# MCU.net
KiCad netlist of a schematic drawn in Altium Designer
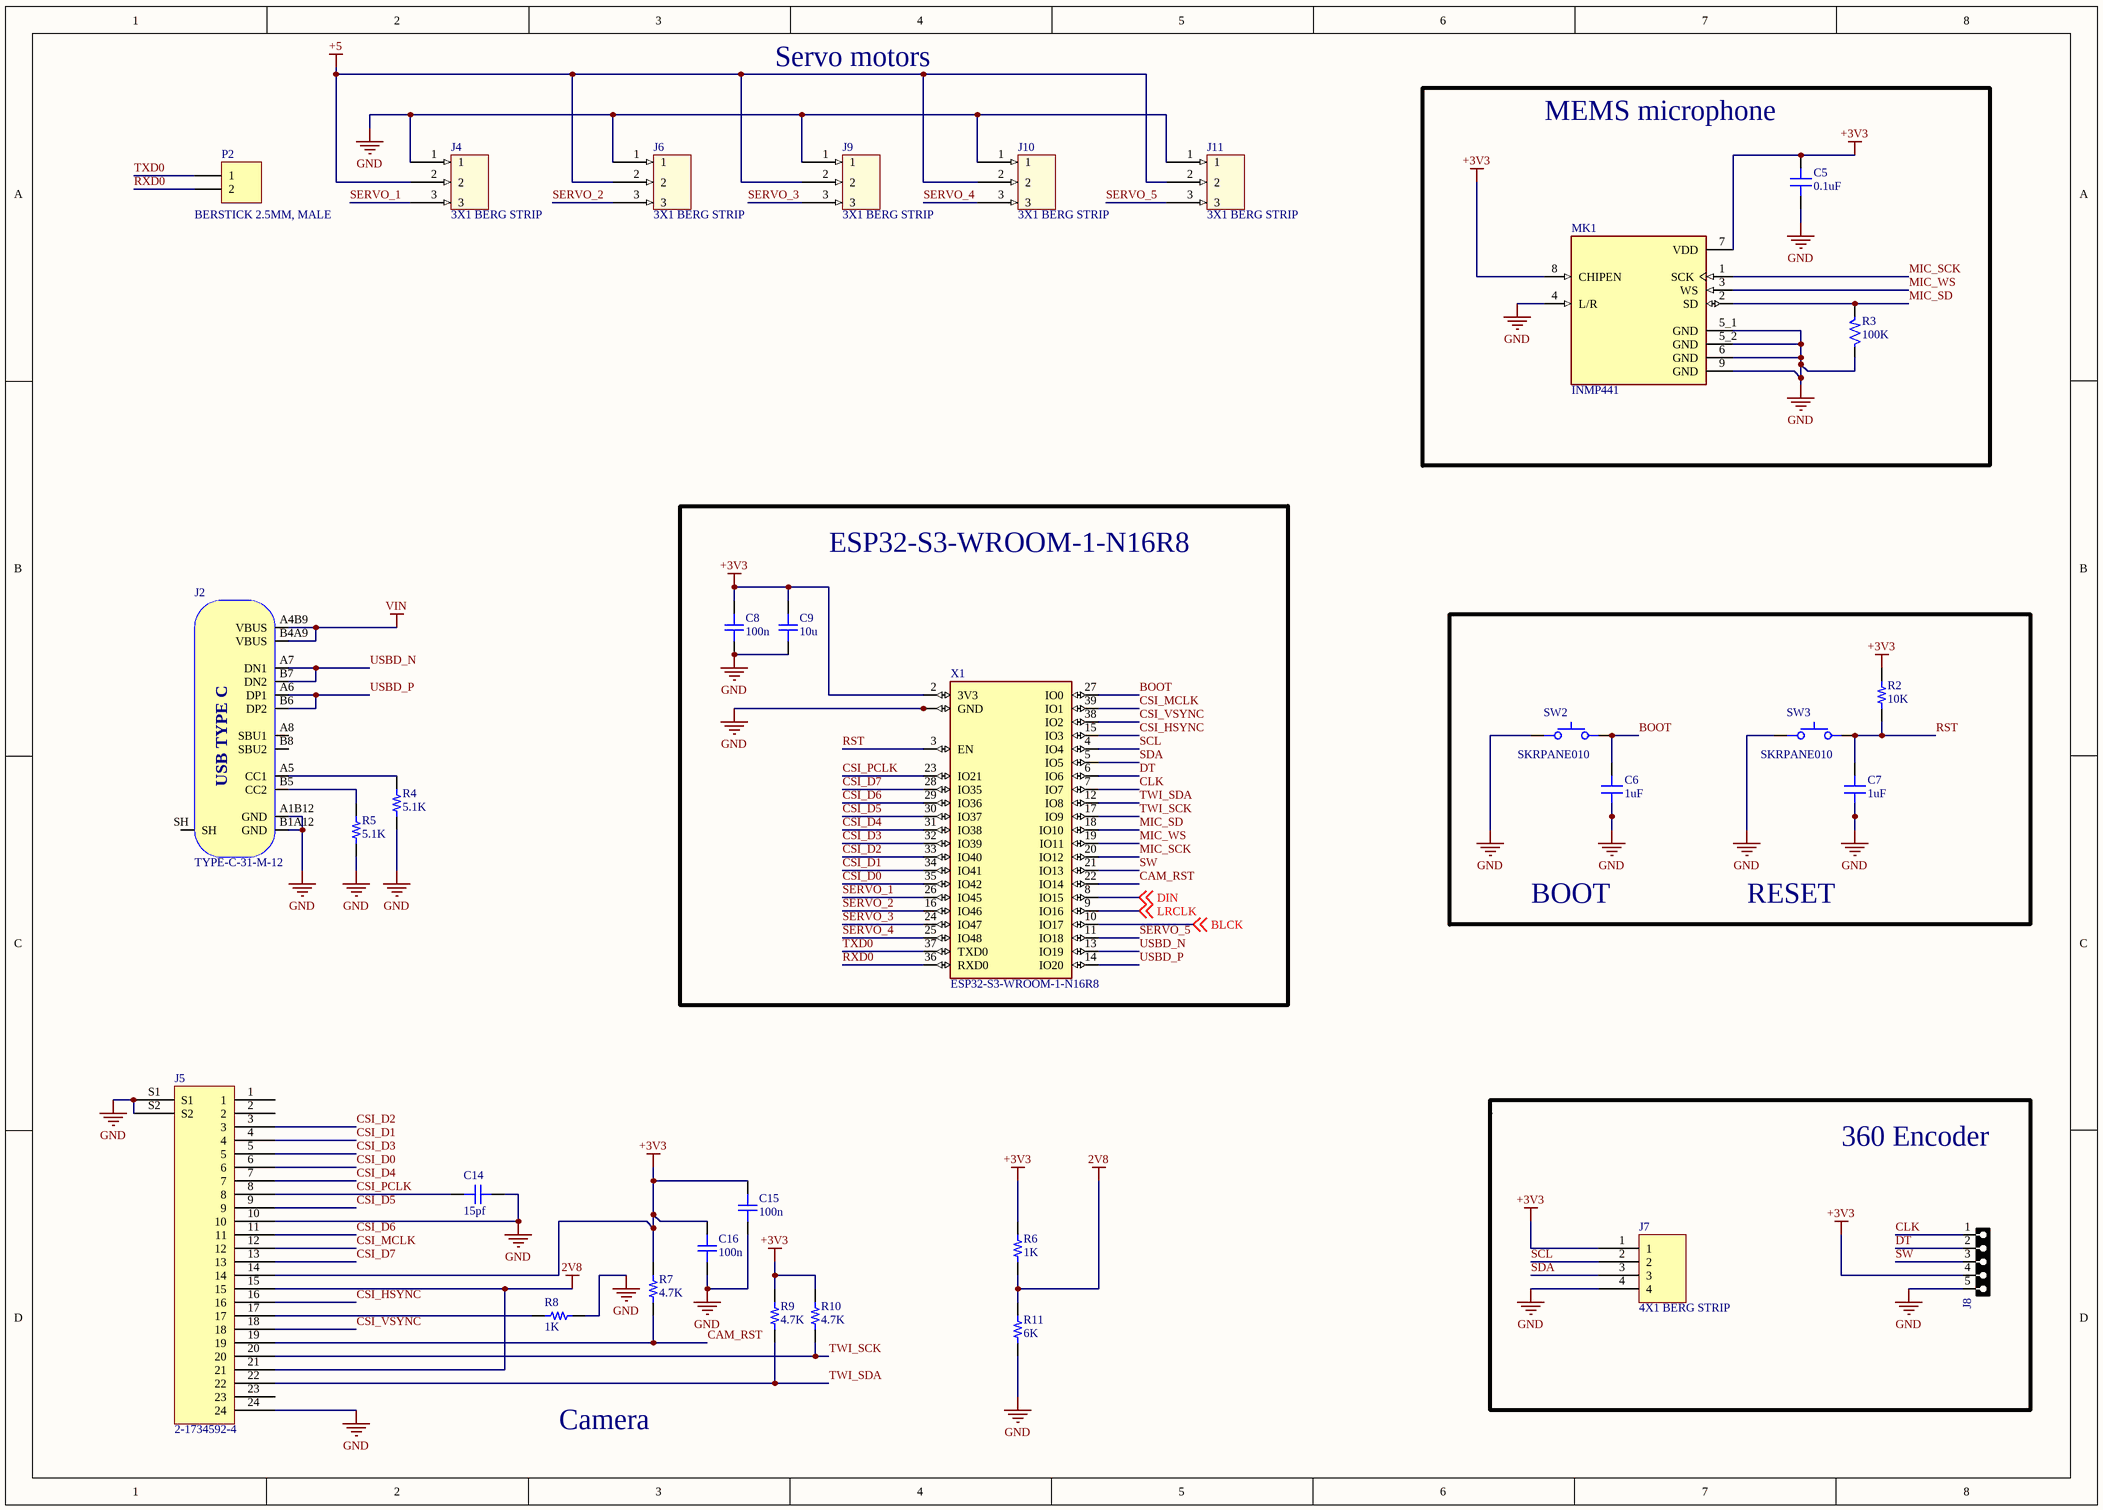
[diagram p0: MCU.SchDoc]

(export (version "E")
  (design (tool "Eeschema 10.0.6"))
  (components
    (comp (ref "C5")
      (value "0.1uF")
      (footprint "CAP 0402_1005")
      (description "SMT Capacitor")
      (libsource (lib "Capacitor") (part "Cap 0402"))
    )
    (comp (ref "C6")
      (value "1uF")
      (footprint "CAP 0402_1005")
      (description "SMT Capacitor")
      (libsource (lib "Capacitor") (part "Cap 0402"))
    )
    (comp (ref "C7")
      (value "1uF")
      (footprint "CAP 0402_1005")
      (description "SMT Capacitor")
      (libsource (lib "Capacitor") (part "Cap 0402"))
    )
    (comp (ref "C8")
      (value "100n")
      (footprint "CAP_0402")
      (description "Capacitor SMD 0402 50V")
      (fields
        (field (name "MANUFACTURER") "Samsung")
        (field (name "MANUFACTURER PART NUMBER") "CL05B104KO5NNNC")
      )
      (libsource (lib "ESP32_USB_Dongle") (part "CAP_0402_50V_1"))
    )
    (comp (ref "C9")
      (value "10u")
      (footprint "CAP_0603")
      (description "Capacitor SMD 0603 10V")
      (fields
        (field (name "MANUFACTURER") "Samsung")
        (field (name "MANUFACTURER PART NUMBER") "CL10A106KP8NNNC")
      )
      (libsource (lib "ESP32_USB_Dongle") (part "CAP_0603_10V"))
    )
    (comp (ref "C14")
      (value "15pf")
      (footprint "CAP_0402")
      (description "Capacitor SMD 0402 50V")
      (fields
        (field (name "MANUFACTURER") "Samsung")
        (field (name "MANUFACTURER PART NUMBER") "CL05C100JB5NNNC")
      )
      (libsource (lib "ESP32_USB_Dongle") (part "CAP_0402_50V_2"))
    )
    (comp (ref "C15")
      (value "100n")
      (footprint "CAP_0402")
      (description "Capacitor SMD 0402 50V")
      (fields
        (field (name "MANUFACTURER") "Samsung")
        (field (name "MANUFACTURER PART NUMBER") "CL05B104KO5NNNC")
      )
      (libsource (lib "ESP32_USB_Dongle") (part "CAP_0402_50V_1"))
    )
    (comp (ref "C16")
      (value "100n")
      (footprint "CAP_0402")
      (description "Capacitor SMD 0402 50V")
      (fields
        (field (name "MANUFACTURER") "Samsung")
        (field (name "MANUFACTURER PART NUMBER") "CL05B104KO5NNNC")
      )
      (libsource (lib "ESP32_USB_Dongle") (part "CAP_0402_50V_1"))
    )
    (comp (ref "J2")
      (value "TYPE-C-31-M-12")
      (footprint "TYPE-C-31-M-12")
      (description "USB Type C Connector Horizontal SMT")
      (fields (field (name "MANUFACTURER") "Koren Hroparts"))
      (libsource (lib "ESP32_USB_Dongle") (part "TYPE-C-31-M-12"))
    )
    (comp (ref "J4")
      (value "3X1 BERG STRIP")
      (footprint "CON3_100_40D72_TH_ST-MALE")
      (description "3 Pins, 1 Row 2.54mm Pitch, Straight bergstrip, Male")
      (fields (field (name "MANUFACTURER PART NUMBER") "RKI-1140") (field (name "MANUFACTURER") "NA"))
      (libsource (lib "ESTEEMPCBLIB") (part "CON-BS-PLG_3X1-100-ST-TH"))
    )
    (comp (ref "J5")
      (value "2-1734592-4")
      (footprint "CON24_19_2-1734592-4_SMD_RA")
      (description "FFC & FPC Connectors FPC CONN 0.5MM PITCH B/C 24P")
      (fields
        (field (name "MANUFACTURER") "TE Connectivity")
        (field (name "MATING PART NUMBER") "0151660259")
      )
      (libsource (lib "ESTEEMPCBLIB") (part "CON-PLG-FPC_24X1-19-RA-BC-SMD"))
    )
    (comp (ref "J6")
      (value "3X1 BERG STRIP")
      (footprint "CON3_100_40D72_TH_ST-MALE")
      (description "3 Pins, 1 Row 2.54mm Pitch, Straight bergstrip, Male")
      (fields (field (name "MANUFACTURER PART NUMBER") "RKI-1140") (field (name "MANUFACTURER") "NA"))
      (libsource (lib "ESTEEMPCBLIB") (part "CON-BS-PLG_3X1-100-ST-TH"))
    )
    (comp (ref "J7")
      (value "4X1 BERG STRIP")
      (footprint "CON4_100_40D72_TH_ST_MALE")
      (description "4 Pins, 1 Row 2.54mm Pitch, Straight bergstrip, Male")
      (fields (field (name "MANUFACTURER") "NA"))
      (libsource (lib "ESTEEMPCBLIB") (part "CON-BS-PLG_4X1-100-ST-TH"))
    )
    (comp (ref "J8")
      (value "HDRF5")
      (footprint "HDRLP_F_1X5")
      (description "CONN, HEADER, Male, pitch: 2.54mm, 5POS")
      (libsource (lib "Conn Header") (part "HDRLP_F_1X5"))
    )
    (comp (ref "J9")
      (value "3X1 BERG STRIP")
      (footprint "CON3_100_40D72_TH_ST-MALE")
      (description "3 Pins, 1 Row 2.54mm Pitch, Straight bergstrip, Male")
      (fields (field (name "MANUFACTURER PART NUMBER") "RKI-1140") (field (name "MANUFACTURER") "NA"))
      (libsource (lib "ESTEEMPCBLIB") (part "CON-BS-PLG_3X1-100-ST-TH"))
    )
    (comp (ref "J10")
      (value "3X1 BERG STRIP")
      (footprint "CON3_100_40D72_TH_ST-MALE")
      (description "3 Pins, 1 Row 2.54mm Pitch, Straight bergstrip, Male")
      (fields (field (name "MANUFACTURER PART NUMBER") "RKI-1140") (field (name "MANUFACTURER") "NA"))
      (libsource (lib "ESTEEMPCBLIB") (part "CON-BS-PLG_3X1-100-ST-TH"))
    )
    (comp (ref "J11")
      (value "3X1 BERG STRIP")
      (footprint "CON3_100_40D72_TH_ST-MALE")
      (description "3 Pins, 1 Row 2.54mm Pitch, Straight bergstrip, Male")
      (fields (field (name "MANUFACTURER PART NUMBER") "RKI-1140") (field (name "MANUFACTURER") "NA"))
      (libsource (lib "ESTEEMPCBLIB") (part "CON-BS-PLG_3X1-100-ST-TH"))
    )
    (comp (ref "MK1")
      (value "INMP441")
      (footprint "MIC_INMP441")
      (description "EVAL BOARD MEMS MIC INMP441")
      (fields (field (name "MF") "TDK InvenSense"))
      (libsource (lib "INMP441") (part "INMP441"))
    )
    (comp (ref "P2")
      (value "BERSTICK 2.5MM, MALE")
      (footprint "CON2_100_43D62_TH_ST")
      (description "2 Pins, 1 Row 2.54mm Pitch, Straight bergstrip, Male")
      (fields (field (name "MANUFACTURER PART NUMBER") "NA") (field (name "MANUFACTURER") "Samtec"))
      (libsource (lib "ESTEEMPCBLIB") (part "CON-BS-PLG_2X1-100-ST-TH"))
    )
    (comp (ref "R2")
      (value "10K")
      (footprint "RES 0402_1005")
      (description "SMT Resistor")
      (libsource (lib "Resistor") (part "Res 0402"))
    )
    (comp (ref "R3")
      (value "100K")
      (footprint "RES_0603")
      (description "100 kOhms ±1% 0.1W, 1/10W Chip Resistor 0603 (1608 Metric) Automotive AEC-Q200 Thick Film")
      (fields
        (field (name "MANUFACTURER") "Stackpole Electronics")
        (field (name "MANUFACTURER PART NUMBER") "RMCF0603FT100K")
      )
      (libsource (lib "ESTEEMPCBLIB") (part "RES_100K-0.1W-1%-0603"))
    )
    (comp (ref "R4")
      (value "5.1K")
      (footprint "RES 0402_1005")
      (description "SMT Resistor")
      (libsource (lib "Resistor") (part "Res 0402"))
    )
    (comp (ref "R5")
      (value "5.1K")
      (footprint "RES 0402_1005")
      (description "SMT Resistor")
      (libsource (lib "Resistor") (part "Res 0402"))
    )
    (comp (ref "R6")
      (value "1K")
      (footprint "RES 0402_1005")
      (description "SMT Resistor")
      (libsource (lib "Resistor") (part "Res 0402"))
    )
    (comp (ref "R7")
      (value "4.7K")
      (footprint "RES 0402_1005")
      (description "SMT Resistor")
      (libsource (lib "Resistor") (part "Res 0402"))
    )
    (comp (ref "R8")
      (value "1K")
      (footprint "RES 0402_1005")
      (description "SMT Resistor")
      (libsource (lib "Resistor") (part "Res 0402"))
    )
    (comp (ref "R9")
      (value "4.7K")
      (footprint "RES 0402_1005")
      (description "SMT Resistor")
      (libsource (lib "Resistor") (part "Res 0402"))
    )
    (comp (ref "R10")
      (value "4.7K")
      (footprint "RES 0402_1005")
      (description "SMT Resistor")
      (libsource (lib "Resistor") (part "Res 0402"))
    )
    (comp (ref "R11")
      (value "6K")
      (footprint "RES 0402_1005")
      (description "SMT Resistor")
      (libsource (lib "Resistor") (part "Res 0402"))
    )
    (comp (ref "SW2")
      (value "SKRPANE010")
      (footprint "SKRPANE010")
      (description "Tactile Switch SMD SPST")
      (fields (field (name "MANUFACTURER") "Alps Alpine"))
      (libsource (lib "ESP32_USB_Dongle") (part "SKRPANE010"))
    )
    (comp (ref "SW3")
      (value "SKRPANE010")
      (footprint "SKRPANE010")
      (description "Tactile Switch SMD SPST")
      (fields (field (name "MANUFACTURER") "Alps Alpine"))
      (libsource (lib "ESP32_USB_Dongle") (part "SKRPANE010"))
    )
    (comp (ref "X1")
      (value "ESP32-S3-WROOM-1-N16R8")
      (footprint "ESP32S3WROOM1N8R2")
      (description "Bluetooth, WiFi 802.11b/g/n, Bluetooth v5.0 Transceiver Module 2.4GHz PCB Trace Surface Mount")
      (fields (field (name "MF") "Espressif Systems"))
      (libsource (lib "ESP32-S3-WROOM-1-N16R8") (part "ESP32-S3-WROOM-1-N16R8"))
    )
  )
  (nets
    (net (code "1") (name "+3V3") (class "Default")
      (node (ref "C15") (pin "2") (pinfunction "2_2") (pintype "passive"))
      (node (ref "C16") (pin "2") (pinfunction "2_2") (pintype "passive"))
      (node (ref "C5") (pin "2") (pinfunction "2_2") (pintype "passive"))
      (node (ref "C8") (pin "2") (pinfunction "2_2") (pintype "passive"))
      (node (ref "C9") (pin "2") (pinfunction "2_2") (pintype "passive"))
      (node (ref "J5") (pin "14") (pinfunction "14_14") (pintype "passive"))
      (node (ref "J7") (pin "1") (pinfunction "1_1") (pintype "passive"))
      (node (ref "J8") (pin "4") (pinfunction "4_4") (pintype "passive"))
      (node (ref "MK1") (pin "7") (pinfunction "VDD_7") (pintype "power_in"))
      (node (ref "MK1") (pin "8") (pinfunction "CHIPEN_8") (pintype "input"))
      (node (ref "R10") (pin "2") (pinfunction "2_2") (pintype "passive"))
      (node (ref "R2") (pin "2") (pinfunction "2_2") (pintype "passive"))
      (node (ref "R6") (pin "2") (pinfunction "2_2") (pintype "passive"))
      (node (ref "R7") (pin "2") (pinfunction "2_2") (pintype "passive"))
      (node (ref "R9") (pin "2") (pinfunction "2_2") (pintype "passive"))
      (node (ref "X1") (pin "2") (pinfunction "3V3_2") (pintype "bidirectional"))
    )
    (net (code "2") (name "+5") (class "Default")
      (node (ref "J10") (pin "2") (pinfunction "2_2") (pintype "input"))
      (node (ref "J11") (pin "2") (pinfunction "2_2") (pintype "input"))
      (node (ref "J4") (pin "2") (pinfunction "2_2") (pintype "input"))
      (node (ref "J6") (pin "2") (pinfunction "2_2") (pintype "input"))
      (node (ref "J9") (pin "2") (pinfunction "2_2") (pintype "input"))
    )
    (net (code "3") (name "/BOOT") (class "Default")
      (node (ref "C6") (pin "2") (pinfunction "2_2") (pintype "passive"))
      (node (ref "SW2") (pin "34") (pintype "passive"))
      (node (ref "X1") (pin "27") (pinfunction "IO0_27") (pintype "bidirectional"))
    )
    (net (code "4") (name "/CAM_RST") (class "Default")
      (node (ref "J5") (pin "19") (pinfunction "19_19") (pintype "passive"))
      (node (ref "R7") (pin "1") (pinfunction "1_1") (pintype "passive"))
      (node (ref "X1") (pin "22") (pinfunction "IO14_22") (pintype "bidirectional"))
    )
    (net (code "5") (name "/CLK") (class "Default")
      (node (ref "J8") (pin "1") (pinfunction "1_1") (pintype "passive"))
      (node (ref "X1") (pin "7") (pinfunction "IO7_7") (pintype "bidirectional"))
    )
    (net (code "6") (name "/CSI_D0") (class "Default")
      (node (ref "J5") (pin "6") (pinfunction "6_6") (pintype "passive"))
      (node (ref "X1") (pin "35") (pinfunction "IO42_35") (pintype "bidirectional"))
    )
    (net (code "7") (name "/CSI_D1") (class "Default")
      (node (ref "J5") (pin "4") (pinfunction "4_4") (pintype "passive"))
      (node (ref "X1") (pin "34") (pinfunction "IO41_34") (pintype "bidirectional"))
    )
    (net (code "8") (name "/CSI_D2") (class "Default")
      (node (ref "J5") (pin "3") (pinfunction "3_3") (pintype "passive"))
      (node (ref "X1") (pin "33") (pinfunction "IO40_33") (pintype "bidirectional"))
    )
    (net (code "9") (name "/CSI_D3") (class "Default")
      (node (ref "J5") (pin "5") (pinfunction "5_5") (pintype "passive"))
      (node (ref "X1") (pin "32") (pinfunction "IO39_32") (pintype "bidirectional"))
    )
    (net (code "10") (name "/CSI_D4") (class "Default")
      (node (ref "J5") (pin "7") (pinfunction "7_7") (pintype "passive"))
      (node (ref "X1") (pin "31") (pinfunction "IO38_31") (pintype "bidirectional"))
    )
    (net (code "11") (name "/CSI_D5") (class "Default")
      (node (ref "J5") (pin "9") (pinfunction "9_9") (pintype "passive"))
      (node (ref "X1") (pin "30") (pinfunction "IO37_30") (pintype "bidirectional"))
    )
    (net (code "12") (name "/CSI_D6") (class "Default")
      (node (ref "J5") (pin "11") (pinfunction "11_11") (pintype "passive"))
      (node (ref "X1") (pin "29") (pinfunction "IO36_29") (pintype "bidirectional"))
    )
    (net (code "13") (name "/CSI_D7") (class "Default")
      (node (ref "J5") (pin "13") (pinfunction "13_13") (pintype "passive"))
      (node (ref "X1") (pin "28") (pinfunction "IO35_28") (pintype "bidirectional"))
    )
    (net (code "14") (name "/CSI_HSYNC") (class "Default")
      (node (ref "J5") (pin "16") (pinfunction "16_16") (pintype "passive"))
      (node (ref "X1") (pin "15") (pinfunction "IO3_15") (pintype "bidirectional"))
    )
    (net (code "15") (name "/CSI_MCLK") (class "Default")
      (node (ref "J5") (pin "12") (pinfunction "12_12") (pintype "passive"))
      (node (ref "X1") (pin "39") (pinfunction "IO1_39") (pintype "bidirectional"))
    )
    (net (code "16") (name "/CSI_PCLK") (class "Default")
      (node (ref "C14") (pin "2") (pinfunction "2_2") (pintype "passive"))
      (node (ref "J5") (pin "8") (pinfunction "8_8") (pintype "passive"))
      (node (ref "X1") (pin "23") (pinfunction "IO21_23") (pintype "bidirectional"))
    )
    (net (code "17") (name "/CSI_VSYNC") (class "Default")
      (node (ref "J5") (pin "18") (pinfunction "18_18") (pintype "passive"))
      (node (ref "X1") (pin "38") (pinfunction "IO2_38") (pintype "bidirectional"))
    )
    (net (code "18") (name "/DT") (class "Default")
      (node (ref "J8") (pin "2") (pinfunction "2_2") (pintype "passive"))
      (node (ref "X1") (pin "6") (pinfunction "IO6_6") (pintype "bidirectional"))
    )
    (net (code "19") (name "/MIC_SCK") (class "Default")
      (node (ref "MK1") (pin "1") (pinfunction "SCK_1") (pintype "input"))
      (node (ref "X1") (pin "20") (pinfunction "IO12_20") (pintype "bidirectional"))
    )
    (net (code "20") (name "/MIC_SD") (class "Default")
      (node (ref "MK1") (pin "2") (pinfunction "SD_2") (pintype "bidirectional"))
      (node (ref "R3") (pin "2") (pinfunction "2_2") (pintype "passive"))
      (node (ref "X1") (pin "18") (pinfunction "IO10_18") (pintype "bidirectional"))
    )
    (net (code "21") (name "/MIC_WS") (class "Default")
      (node (ref "MK1") (pin "3") (pinfunction "WS_3") (pintype "input"))
      (node (ref "X1") (pin "19") (pinfunction "IO11_19") (pintype "bidirectional"))
    )
    (net (code "22") (name "/RST") (class "Default")
      (node (ref "C7") (pin "2") (pinfunction "2_2") (pintype "passive"))
      (node (ref "R2") (pin "1") (pinfunction "1_1") (pintype "passive"))
      (node (ref "SW3") (pin "34") (pintype "passive"))
      (node (ref "X1") (pin "3") (pinfunction "EN_3") (pintype "bidirectional"))
    )
    (net (code "23") (name "/RXD0") (class "Default")
      (node (ref "P2") (pin "2") (pinfunction "2_2") (pintype "passive"))
      (node (ref "X1") (pin "36") (pinfunction "RXD0_36") (pintype "bidirectional"))
    )
    (net (code "24") (name "/SCL") (class "Default")
      (node (ref "J7") (pin "2") (pinfunction "2_2") (pintype "passive"))
      (node (ref "X1") (pin "4") (pinfunction "IO4_4") (pintype "bidirectional"))
    )
    (net (code "25") (name "/SDA") (class "Default")
      (node (ref "J7") (pin "3") (pinfunction "3_3") (pintype "passive"))
      (node (ref "X1") (pin "5") (pinfunction "IO5_5") (pintype "bidirectional"))
    )
    (net (code "26") (name "/SERVO_1") (class "Default")
      (node (ref "J4") (pin "3") (pinfunction "3_3") (pintype "input"))
      (node (ref "X1") (pin "26") (pinfunction "IO45_26") (pintype "bidirectional"))
    )
    (net (code "27") (name "/SERVO_2") (class "Default")
      (node (ref "J6") (pin "3") (pinfunction "3_3") (pintype "input"))
      (node (ref "X1") (pin "16") (pinfunction "IO46_16") (pintype "bidirectional"))
    )
    (net (code "28") (name "/SERVO_3") (class "Default")
      (node (ref "J9") (pin "3") (pinfunction "3_3") (pintype "input"))
      (node (ref "X1") (pin "24") (pinfunction "IO47_24") (pintype "bidirectional"))
    )
    (net (code "29") (name "/SERVO_4") (class "Default")
      (node (ref "J10") (pin "3") (pinfunction "3_3") (pintype "input"))
      (node (ref "X1") (pin "25") (pinfunction "IO48_25") (pintype "bidirectional"))
    )
    (net (code "30") (name "/SERVO_5") (class "Default")
      (node (ref "J11") (pin "3") (pinfunction "3_3") (pintype "input"))
      (node (ref "X1") (pin "11") (pinfunction "IO18_11") (pintype "bidirectional"))
    )
    (net (code "31") (name "/SW") (class "Default")
      (node (ref "J8") (pin "3") (pinfunction "3_3") (pintype "passive"))
      (node (ref "X1") (pin "21") (pinfunction "IO13_21") (pintype "bidirectional"))
    )
    (net (code "32") (name "/TWI_SCK") (class "Default")
      (node (ref "J5") (pin "20") (pinfunction "20_20") (pintype "passive"))
      (node (ref "R10") (pin "1") (pinfunction "1_1") (pintype "passive"))
      (node (ref "X1") (pin "17") (pinfunction "IO9_17") (pintype "bidirectional"))
    )
    (net (code "33") (name "/TWI_SDA") (class "Default")
      (node (ref "J5") (pin "22") (pinfunction "22_22") (pintype "passive"))
      (node (ref "R9") (pin "1") (pinfunction "1_1") (pintype "passive"))
      (node (ref "X1") (pin "12") (pinfunction "IO8_12") (pintype "bidirectional"))
    )
    (net (code "34") (name "/TXD0") (class "Default")
      (node (ref "P2") (pin "1") (pinfunction "1_1") (pintype "passive"))
      (node (ref "X1") (pin "37") (pinfunction "TXD0_37") (pintype "bidirectional"))
    )
    (net (code "35") (name "/USBD_N") (class "Default")
      (node (ref "J2") (pin "A7") (pinfunction "DN1_A7") (pintype "bidirectional"))
      (node (ref "J2") (pin "B7") (pinfunction "DN2_B7") (pintype "bidirectional"))
      (node (ref "X1") (pin "13") (pinfunction "IO19_13") (pintype "bidirectional"))
    )
    (net (code "36") (name "/USBD_P") (class "Default")
      (node (ref "J2") (pin "A6") (pinfunction "DP1_A6") (pintype "bidirectional"))
      (node (ref "J2") (pin "B6") (pinfunction "DP2_B6") (pintype "bidirectional"))
      (node (ref "X1") (pin "14") (pinfunction "IO20_14") (pintype "bidirectional"))
    )
    (net (code "37") (name "2V8") (class "Default")
      (node (ref "J5") (pin "15") (pinfunction "15_15") (pintype "passive"))
      (node (ref "J5") (pin "21") (pinfunction "21_21") (pintype "passive"))
      (node (ref "R11") (pin "2") (pinfunction "2_2") (pintype "passive"))
      (node (ref "R6") (pin "1") (pinfunction "1_1") (pintype "passive"))
    )
    (net (code "38") (name "BLCK") (class "Default")
      (node (ref "X1") (pin "10") (pinfunction "IO17_10") (pintype "bidirectional"))
    )
    (net (code "39") (name "DIN") (class "Default")
      (node (ref "X1") (pin "8") (pinfunction "IO15_8") (pintype "bidirectional"))
    )
    (net (code "40") (name "GND") (class "Default")
      (node (ref "C14") (pin "1") (pinfunction "1_1") (pintype "passive"))
      (node (ref "C15") (pin "1") (pinfunction "1_1") (pintype "passive"))
      (node (ref "C16") (pin "1") (pinfunction "1_1") (pintype "passive"))
      (node (ref "C5") (pin "1") (pinfunction "1_1") (pintype "passive"))
      (node (ref "C6") (pin "1") (pinfunction "1_1") (pintype "passive"))
      (node (ref "C7") (pin "1") (pinfunction "1_1") (pintype "passive"))
      (node (ref "C8") (pin "1") (pinfunction "1_1") (pintype "passive"))
      (node (ref "C9") (pin "1") (pinfunction "1_1") (pintype "passive"))
      (node (ref "J10") (pin "1") (pinfunction "1_1") (pintype "input"))
      (node (ref "J11") (pin "1") (pinfunction "1_1") (pintype "input"))
      (node (ref "J2") (pin "A1B12") (pinfunction "GND_A1B12") (pintype "power_in"))
      (node (ref "J2") (pin "B1A12") (pinfunction "GND_B1A12") (pintype "power_in"))
      (node (ref "J4") (pin "1") (pinfunction "1_1") (pintype "input"))
      (node (ref "J5") (pin "10") (pinfunction "10_10") (pintype "passive"))
      (node (ref "J5") (pin "24") (pinfunction "24_24") (pintype "passive"))
      (node (ref "J5") (pin "S1") (pinfunction "S1_S1") (pintype "passive"))
      (node (ref "J5") (pin "S2") (pinfunction "S2_S2") (pintype "passive"))
      (node (ref "J6") (pin "1") (pinfunction "1_1") (pintype "input"))
      (node (ref "J7") (pin "4") (pinfunction "4_4") (pintype "passive"))
      (node (ref "J8") (pin "5") (pinfunction "5_5") (pintype "passive"))
      (node (ref "J9") (pin "1") (pinfunction "1_1") (pintype "input"))
      (node (ref "MK1") (pin "4") (pinfunction "L/R_4") (pintype "input"))
      (node (ref "MK1") (pin "5_1") (pinfunction "GND_5_1") (pintype "power_in"))
      (node (ref "MK1") (pin "5_2") (pinfunction "GND_5_2") (pintype "power_in"))
      (node (ref "MK1") (pin "6") (pinfunction "GND_6") (pintype "power_in"))
      (node (ref "MK1") (pin "9") (pinfunction "GND_9") (pintype "power_in"))
      (node (ref "R11") (pin "1") (pinfunction "1_1") (pintype "passive"))
      (node (ref "R3") (pin "1") (pinfunction "1_1") (pintype "passive"))
      (node (ref "R4") (pin "1") (pinfunction "1_1") (pintype "passive"))
      (node (ref "R5") (pin "1") (pinfunction "1_1") (pintype "passive"))
      (node (ref "R8") (pin "1") (pinfunction "1_1") (pintype "passive"))
      (node (ref "SW2") (pin "12") (pintype "passive"))
      (node (ref "SW3") (pin "12") (pintype "passive"))
      (node (ref "X1") (pin "1") (pinfunction "GND_1") (pintype "bidirectional"))
      (node (ref "X1") (pin "40") (pinfunction "GND_40") (pintype "bidirectional"))
      (node (ref "X1") (pin "41") (pinfunction "GND_41") (pintype "bidirectional"))
      (node (ref "X1") (pin "42") (pinfunction "GND_42") (pintype "bidirectional"))
      (node (ref "X1") (pin "43") (pinfunction "GND_43") (pintype "bidirectional"))
      (node (ref "X1") (pin "44") (pinfunction "GND_44") (pintype "bidirectional"))
      (node (ref "X1") (pin "45") (pinfunction "GND_45") (pintype "bidirectional"))
      (node (ref "X1") (pin "46") (pinfunction "GND_46") (pintype "bidirectional"))
      (node (ref "X1") (pin "47") (pinfunction "GND_47") (pintype "bidirectional"))
      (node (ref "X1") (pin "48") (pinfunction "GND_48") (pintype "bidirectional"))
      (node (ref "X1") (pin "49") (pinfunction "GND_49") (pintype "bidirectional"))
    )
    (net (code "41") (name "LRCLK") (class "Default")
      (node (ref "X1") (pin "9") (pinfunction "IO16_9") (pintype "bidirectional"))
    )
    (net (code "42") (name "Net-(J2-CC1)") (class "Default")
      (node (ref "J2") (pin "A5") (pinfunction "CC1_A5") (pintype "passive"))
      (node (ref "R4") (pin "2") (pinfunction "2_2") (pintype "passive"))
    )
    (net (code "43") (name "Net-(J2-CC2)") (class "Default")
      (node (ref "J2") (pin "B5") (pinfunction "CC2_B5") (pintype "tri_state"))
      (node (ref "R5") (pin "2") (pinfunction "2_2") (pintype "passive"))
    )
    (net (code "44") (name "Net-(J5-Pad17)") (class "Default")
      (node (ref "J5") (pin "17") (pinfunction "17_17") (pintype "passive"))
      (node (ref "R8") (pin "2") (pinfunction "2_2") (pintype "passive"))
    )
    (net (code "45") (name "VIN") (class "Default")
      (node (ref "J2") (pin "A4B9") (pinfunction "VBUS_A4B9") (pintype "power_in"))
      (node (ref "J2") (pin "B4A9") (pinfunction "VBUS_B4A9") (pintype "power_in"))
    )
    (net (code "46") (name "unconnected-(J2-PadSH)") (class "Default")
      (node (ref "J2") (pin "SH") (pinfunction "SH_SH") (pintype "power_in"))
    )
    (net (code "47") (name "unconnected-(J2-SBU1-PadA8)") (class "Default")
      (node (ref "J2") (pin "A8") (pinfunction "SBU1_A8") (pintype "bidirectional"))
    )
    (net (code "48") (name "unconnected-(J2-SBU2-PadB8)") (class "Default")
      (node (ref "J2") (pin "B8") (pinfunction "SBU2_B8") (pintype "bidirectional"))
    )
    (net (code "49") (name "unconnected-(J5-Pad1)") (class "Default")
      (node (ref "J5") (pin "1") (pinfunction "1_1") (pintype "passive"))
    )
    (net (code "50") (name "unconnected-(J5-Pad2)") (class "Default")
      (node (ref "J5") (pin "2") (pinfunction "2_2") (pintype "passive"))
    )
    (net (code "51") (name "unconnected-(J5-Pad23)") (class "Default")
      (node (ref "J5") (pin "23") (pinfunction "23_23") (pintype "passive"))
    )
  )
)
